# clock_12MHz.net
KiCad netlist of a schematic drawn in Altium Designer
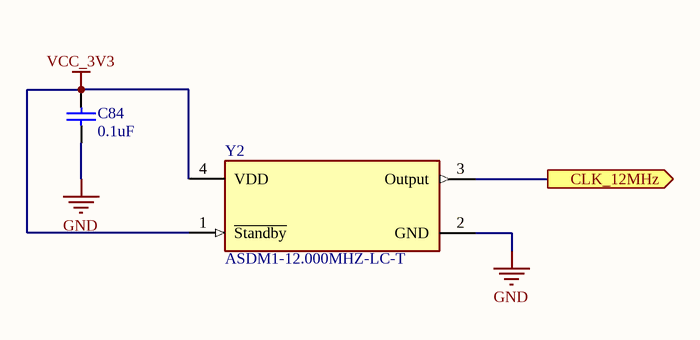
[diagram p0: clock_12MHz.SchDoc]

(export (version "E")
  (design (tool "Eeschema 10.0.6"))
  (components
    (comp (ref "C84")
      (value "0.1uF")
      (footprint "0805_C_S")
      (description "Capacitor")
      (fields (field (name "PUBLISHER") "Altium Limited"))
      (libsource (lib "Miscellaneous Devices") (part "Cap"))
    )
    (comp (ref "Y2")
      (value "ASDM1-12.000MHZ-LC-T")
      (footprint "FP-ASDM-ASDMB-MFG")
      (description "MEMS Oscillator 12MHz ±50ppm LVCMOS 3.3V SMD 2.5x2mm")
      (libsource (lib "Altium Content Vault") (part "d1c68ac5f38726358044f3b7e06346c"))
    )
  )
  (nets
    (net (code "1") (name "/CLK_12MHz") (class "Default")
      (node (ref "Y2") (pin "3") (pinfunction "Output_3") (pintype "output"))
    )
    (net (code "2") (name "GND") (class "Default")
      (node (ref "C84") (pin "1") (pinfunction "1_1") (pintype "passive"))
      (node (ref "Y2") (pin "2") (pinfunction "GND_2") (pintype "power_in"))
    )
    (net (code "3") (name "VCC_3V3") (class "Default")
      (node (ref "C84") (pin "2") (pinfunction "2_2") (pintype "passive"))
      (node (ref "Y2") (pin "1") (pinfunction "~{Standby}_1") (pintype "input"))
      (node (ref "Y2") (pin "4") (pinfunction "VDD_4") (pintype "power_in"))
    )
  )
)
